# schematics.net
KiCad netlist of a schematic drawn in EAGLE
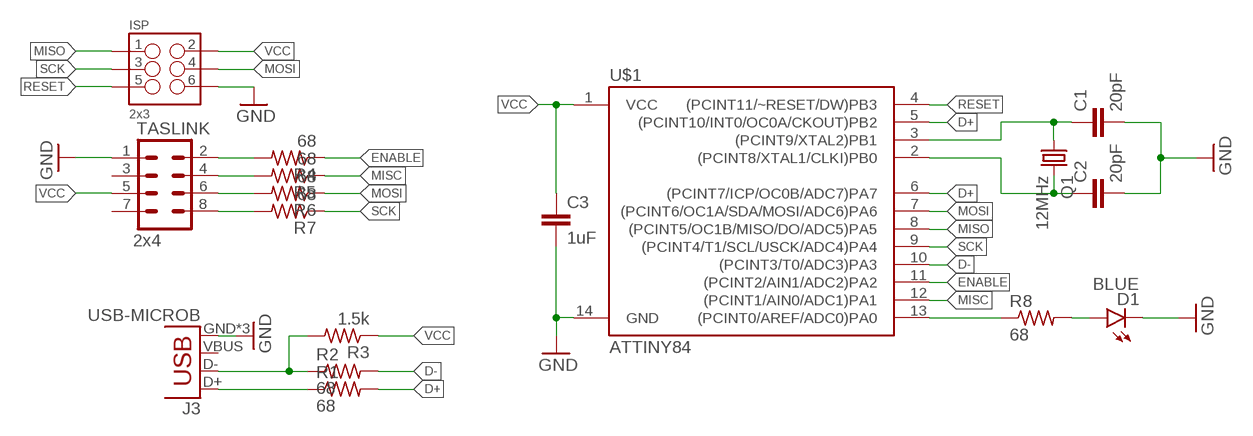
[diagram p0: schematic, sheet 1]

(export (version "E")
  (design (tool "Eeschema 10.0.6"))
  (components
    (comp (ref "C1")
      (value "20pF")
      (footprint "eagle-import:C0603")
      (libsource (lib "eagle-import") (part "C-EUC0603"))
    )
    (comp (ref "C2")
      (value "20pF")
      (footprint "eagle-import:C0603")
      (libsource (lib "eagle-import") (part "C-EUC0603"))
    )
    (comp (ref "C3")
      (value "1uF")
      (footprint "eagle-import:C0603")
      (libsource (lib "eagle-import") (part "C-EUC0603"))
    )
    (comp (ref "D1")
      (value "BLUE")
      (footprint "eagle-import:LED-0603")
      (libsource (lib "eagle-import") (part "LED-BLUE0603"))
    )
    (comp (ref "ISP")
      (value "2x3")
      (footprint "eagle-import:2X3_POGO")
      (libsource (lib "eagle-import") (part "M03X2POGO_PINS"))
    )
    (comp (ref "J3")
      (value "USB-MICROB")
      (footprint "eagle-import:USB-MICROB")
      (libsource (lib "eagle-import") (part "USB-MICROB"))
    )
    (comp (ref "Q1")
      (value "12MHz")
      (footprint "eagle-import:CTS406")
      (libsource (lib "eagle-import") (part "CRYSTALCTS406"))
    )
    (comp (ref "R1")
      (value "68")
      (footprint "eagle-import:R0603")
      (libsource (lib "eagle-import") (part "R-US_R0603"))
    )
    (comp (ref "R2")
      (value "68")
      (footprint "eagle-import:R0603")
      (libsource (lib "eagle-import") (part "R-US_R0603"))
    )
    (comp (ref "R3")
      (value "1.5k")
      (footprint "eagle-import:R0603")
      (libsource (lib "eagle-import") (part "R-US_R0603"))
    )
    (comp (ref "R4")
      (value "68")
      (footprint "eagle-import:R0603")
      (libsource (lib "eagle-import") (part "R-US_R0603"))
    )
    (comp (ref "R5")
      (value "68")
      (footprint "eagle-import:R0603")
      (libsource (lib "eagle-import") (part "R-US_R0603"))
    )
    (comp (ref "R6")
      (value "68")
      (footprint "eagle-import:R0603")
      (libsource (lib "eagle-import") (part "R-US_R0603"))
    )
    (comp (ref "R7")
      (value "68")
      (footprint "eagle-import:R0603")
      (libsource (lib "eagle-import") (part "R-US_R0603"))
    )
    (comp (ref "R8")
      (value "68")
      (footprint "eagle-import:R0603")
      (libsource (lib "eagle-import") (part "R-US_R0603"))
    )
    (comp (ref "TASLINK")
      (value "2x4")
      (footprint "eagle-import:2X4")
      (libsource (lib "eagle-import") (part "M04X2"))
    )
    (comp (ref "U$1")
      (value "ATTINY84")
      (footprint "eagle-import:SO14")
      (libsource (lib "eagle-import") (part "ATTINY84"))
    )
  )
  (nets
    (net (code "1") (name "D+") (class "Default")
      (node (ref "R1") (pin "2") (pinfunction "2_2") (pintype "passive"))
      (node (ref "U$1") (pin "5") (pinfunction "(PCINT10/INT0/OC0A/CKOUT)PB2_5") (pintype "bidirectional"))
      (node (ref "U$1") (pin "6") (pinfunction "(PCINT7/ICP/OC0B/ADC7)PA7_6") (pintype "bidirectional"))
    )
    (net (code "2") (name "D-") (class "Default")
      (node (ref "R2") (pin "2") (pinfunction "2_2") (pintype "passive"))
      (node (ref "U$1") (pin "10") (pinfunction "(PCINT3/T0/ADC3)PA3_10") (pintype "bidirectional"))
    )
    (net (code "3") (name "ENABLE") (class "Default")
      (node (ref "R4") (pin "1") (pinfunction "1_1") (pintype "passive"))
      (node (ref "U$1") (pin "11") (pinfunction "(PCINT2/AIN1/ADC2)PA2_11") (pintype "bidirectional"))
    )
    (net (code "4") (name "GND") (class "Default")
      (node (ref "C1") (pin "2") (pinfunction "2_2") (pintype "passive"))
      (node (ref "C2") (pin "2") (pinfunction "2_2") (pintype "passive"))
      (node (ref "C3") (pin "2") (pinfunction "2_2") (pintype "passive"))
      (node (ref "D1") (pin "C") (pinfunction "C_C") (pintype "passive"))
      (node (ref "ISP") (pin "P$6") (pinfunction "6_P$6") (pintype "bidirectional"))
      (node (ref "J3") (pin "GND") (pinfunction "GND_GND") (pintype "bidirectional"))
      (node (ref "J3") (pin "MT1") (pinfunction "GND_MT1") (pintype "bidirectional"))
      (node (ref "J3") (pin "MT2") (pinfunction "GND_MT2") (pintype "bidirectional"))
      (node (ref "TASLINK") (pin "1") (pinfunction "1_1") (pintype "passive"))
      (node (ref "U$1") (pin "14") (pinfunction "GND_14") (pintype "bidirectional"))
    )
    (net (code "5") (name "MISC") (class "Default")
      (node (ref "R5") (pin "1") (pinfunction "1_1") (pintype "passive"))
      (node (ref "U$1") (pin "12") (pinfunction "(PCINT1/AIN0/ADC1)PA1_12") (pintype "bidirectional"))
    )
    (net (code "6") (name "MISO") (class "Default")
      (node (ref "ISP") (pin "P$1") (pinfunction "1_P$1") (pintype "bidirectional"))
      (node (ref "U$1") (pin "8") (pinfunction "(PCINT5/OC1B/MISO/DO/ADC5)PA5_8") (pintype "bidirectional"))
    )
    (net (code "7") (name "MOSI") (class "Default")
      (node (ref "ISP") (pin "P$4") (pinfunction "4_P$4") (pintype "bidirectional"))
      (node (ref "R6") (pin "1") (pinfunction "1_1") (pintype "passive"))
      (node (ref "U$1") (pin "7") (pinfunction "(PCINT6/OC1A/SDA/MOSI/ADC6)PA6_7") (pintype "bidirectional"))
    )
    (net (code "8") (name "Net-(D1-PadA)") (class "Default")
      (node (ref "D1") (pin "A") (pinfunction "A_A") (pintype "passive"))
      (node (ref "R8") (pin "2") (pinfunction "2_2") (pintype "passive"))
    )
    (net (code "9") (name "Net-(J3-PadD+)") (class "Default")
      (node (ref "J3") (pin "D+") (pinfunction "D+_D+") (pintype "bidirectional"))
      (node (ref "R1") (pin "1") (pinfunction "1_1") (pintype "passive"))
    )
    (net (code "10") (name "Net-(J3-PadD-)") (class "Default")
      (node (ref "J3") (pin "D-") (pinfunction "D-_D-") (pintype "bidirectional"))
      (node (ref "R2") (pin "1") (pinfunction "1_1") (pintype "passive"))
      (node (ref "R3") (pin "2") (pinfunction "2_2") (pintype "passive"))
    )
    (net (code "11") (name "Net-(Q1-2)") (class "Default")
      (node (ref "C2") (pin "1") (pinfunction "1_1") (pintype "passive"))
      (node (ref "Q1") (pin "3") (pinfunction "2_3") (pintype "passive"))
      (node (ref "U$1") (pin "2") (pinfunction "(PCINT8/XTAL1/CLKI)PB0_2") (pintype "bidirectional"))
    )
    (net (code "12") (name "Net-(R4-Pad2)") (class "Default")
      (node (ref "R4") (pin "2") (pinfunction "2_2") (pintype "passive"))
      (node (ref "TASLINK") (pin "2") (pinfunction "2_2") (pintype "passive"))
    )
    (net (code "13") (name "Net-(R5-Pad2)") (class "Default")
      (node (ref "R5") (pin "2") (pinfunction "2_2") (pintype "passive"))
      (node (ref "TASLINK") (pin "4") (pinfunction "4_4") (pintype "passive"))
    )
    (net (code "14") (name "Net-(R6-Pad2)") (class "Default")
      (node (ref "R6") (pin "2") (pinfunction "2_2") (pintype "passive"))
      (node (ref "TASLINK") (pin "6") (pinfunction "6_6") (pintype "passive"))
    )
    (net (code "15") (name "Net-(R7-Pad2)") (class "Default")
      (node (ref "R7") (pin "2") (pinfunction "2_2") (pintype "passive"))
      (node (ref "TASLINK") (pin "8") (pinfunction "8_8") (pintype "passive"))
    )
    (net (code "16") (name "Net-(U$1-(PCINT0{slash}AREF{slash}ADC0)PA0)") (class "Default")
      (node (ref "R8") (pin "1") (pinfunction "1_1") (pintype "passive"))
      (node (ref "U$1") (pin "13") (pinfunction "(PCINT0/AREF/ADC0)PA0_13") (pintype "bidirectional"))
    )
    (net (code "17") (name "Net-(U$1-(PCINT9{slash}XTAL2)PB1)") (class "Default")
      (node (ref "C1") (pin "1") (pinfunction "1_1") (pintype "passive"))
      (node (ref "Q1") (pin "1") (pinfunction "1_1") (pintype "passive"))
      (node (ref "U$1") (pin "3") (pinfunction "(PCINT9/XTAL2)PB1_3") (pintype "bidirectional"))
    )
    (net (code "18") (name "RESET") (class "Default")
      (node (ref "ISP") (pin "P$5") (pinfunction "5_P$5") (pintype "bidirectional"))
      (node (ref "U$1") (pin "4") (pinfunction "(PCINT11/~{RESET/DW})PB3_4") (pintype "bidirectional"))
    )
    (net (code "19") (name "SCK") (class "Default")
      (node (ref "ISP") (pin "P$3") (pinfunction "3_P$3") (pintype "bidirectional"))
      (node (ref "R7") (pin "1") (pinfunction "1_1") (pintype "passive"))
      (node (ref "U$1") (pin "9") (pinfunction "(PCINT4/T1/SCL/USCK/ADC4)PA4_9") (pintype "bidirectional"))
    )
    (net (code "20") (name "VCC") (class "Default")
      (node (ref "C3") (pin "1") (pinfunction "1_1") (pintype "passive"))
      (node (ref "ISP") (pin "P$2") (pinfunction "2_P$2") (pintype "bidirectional"))
      (node (ref "R3") (pin "1") (pinfunction "1_1") (pintype "passive"))
      (node (ref "TASLINK") (pin "5") (pinfunction "5_5") (pintype "passive"))
      (node (ref "U$1") (pin "1") (pinfunction "VCC_1") (pintype "bidirectional"))
    )
    (net (code "21") (name "unconnected-(J3-PadVBUS)") (class "Default")
      (node (ref "J3") (pin "VBUS") (pinfunction "VBUS_VBUS") (pintype "bidirectional"))
    )
    (net (code "22") (name "unconnected-(TASLINK-Pad3)") (class "Default")
      (node (ref "TASLINK") (pin "3") (pinfunction "3_3") (pintype "passive"))
    )
    (net (code "23") (name "unconnected-(TASLINK-Pad7)") (class "Default")
      (node (ref "TASLINK") (pin "7") (pinfunction "7_7") (pintype "passive"))
    )
  )
)
